# IMU_Raspberry_Pi_Breakout_RevB.net
KiCad netlist of a schematic drawn in EAGLE
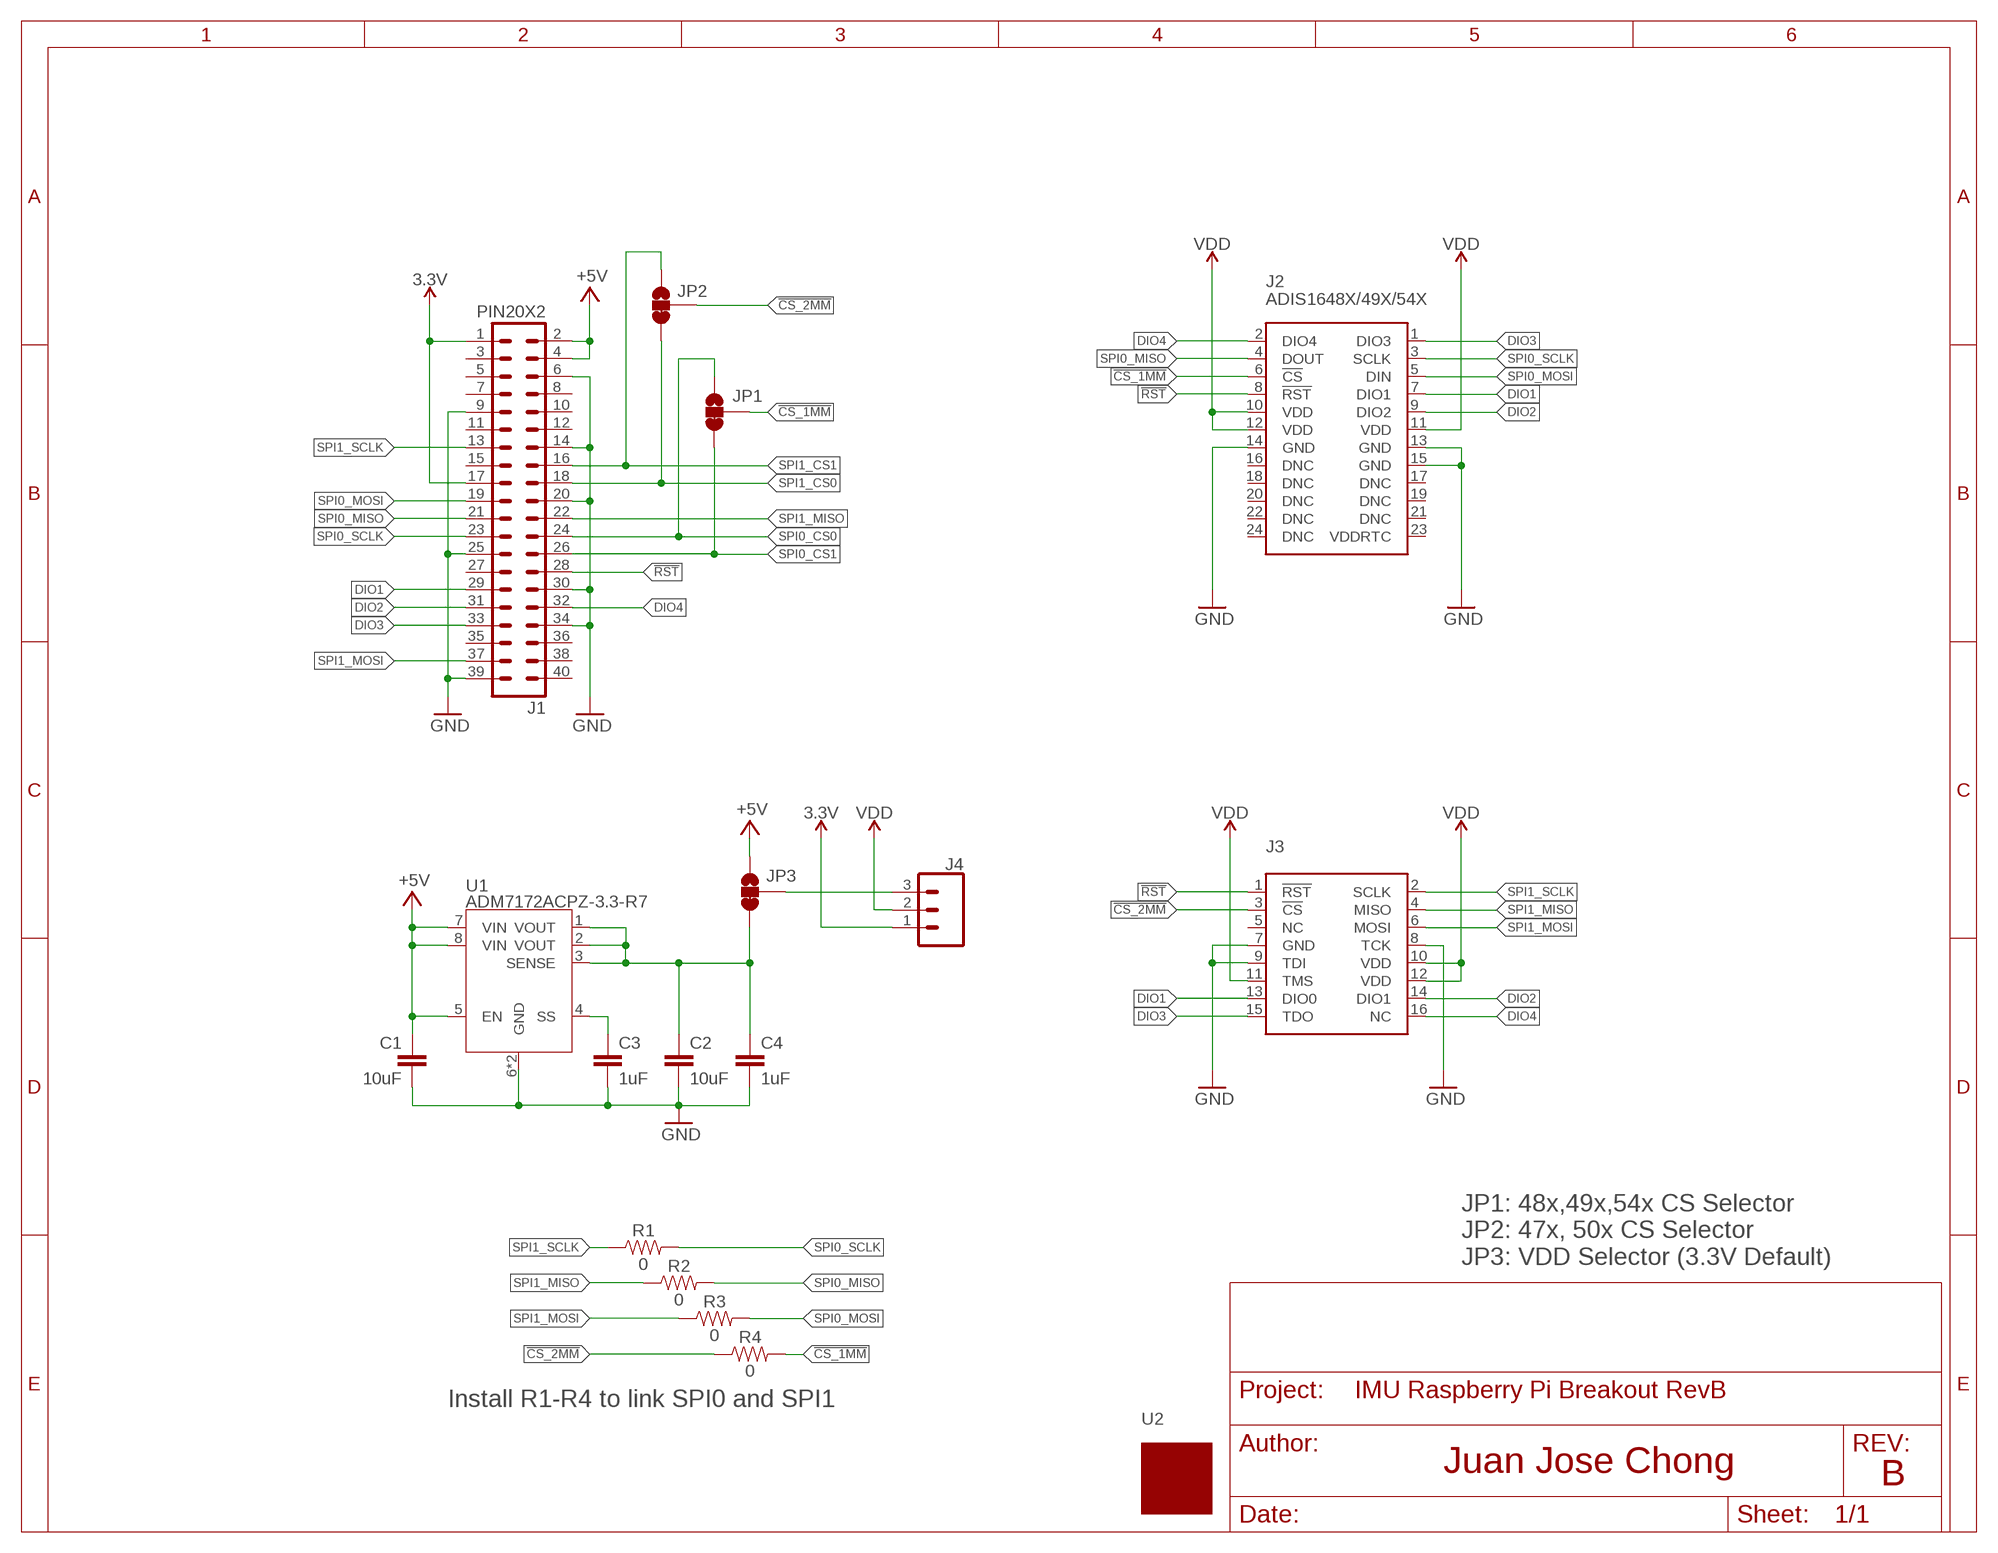
[diagram p0: schematic, sheet 1]

(export (version "E")
  (design (tool "Eeschema 10.0.6"))
  (components
    (comp (ref "C1")
      (value "10uF")
      (footprint "eagle-import:0805")
      (libsource (lib "eagle-import") (part "CAP-0805"))
    )
    (comp (ref "C2")
      (value "10uF")
      (footprint "eagle-import:0805")
      (libsource (lib "eagle-import") (part "CAP-0805"))
    )
    (comp (ref "C3")
      (value "1uF")
      (footprint "eagle-import:0603")
      (libsource (lib "eagle-import") (part "CAP-0603"))
    )
    (comp (ref "C4")
      (value "1uF")
      (footprint "eagle-import:0603")
      (libsource (lib "eagle-import") (part "CAP-0603"))
    )
    (comp (ref "J1")
      (value "PIN20X2")
      (footprint "eagle-import:PIN_20X2")
      (libsource (lib "eagle-import") (part "PIN20X2"))
    )
    (comp (ref "J2")
      (value "ADIS1648X/49X/54X")
      (footprint "eagle-import:ADIS1648X-TAPPED")
      (libsource (lib "eagle-import") (part "ADIS1648X/ADIS1649XTAPPED"))
    )
    (comp (ref "J3")
      (value "ADIS_EVAL_16PIN_2MM")
      (footprint "eagle-import:A3-16PA-2SV(71)-TOP")
      (libsource (lib "eagle-import") (part "ADIS_EVAL_16PIN_2MM"))
    )
    (comp (ref "J4")
      (value "455-1750-1-ND")
      (footprint "eagle-import:1X03")
      (libsource (lib "eagle-import") (part "CONN_03"))
    )
    (comp (ref "JP1")
      (value "JUMPER-SMT_3_1-NC_TRACE_SILK")
      (footprint "eagle-import:SMT-JUMPER_3_1-NC_TRACE_SILK")
      (libsource (lib "eagle-import") (part "JUMPER-SMT_3_1-NC_TRACE_SILK"))
    )
    (comp (ref "JP2")
      (value "JUMPER-SMT_3_1-NC_TRACE_SILK")
      (footprint "eagle-import:SMT-JUMPER_3_1-NC_TRACE_SILK")
      (libsource (lib "eagle-import") (part "JUMPER-SMT_3_1-NC_TRACE_SILK"))
    )
    (comp (ref "JP3")
      (value "JUMPER-SMT_3_1-NC_TRACE_SILK")
      (footprint "eagle-import:SMT-JUMPER_3_1-NC_TRACE_SILK")
      (libsource (lib "eagle-import") (part "JUMPER-SMT_3_1-NC_TRACE_SILK"))
    )
    (comp (ref "R1")
      (value "0")
      (footprint "eagle-import:0603")
      (libsource (lib "eagle-import") (part "RESISTOR0603"))
    )
    (comp (ref "R2")
      (value "0")
      (footprint "eagle-import:0603")
      (libsource (lib "eagle-import") (part "RESISTOR0603"))
    )
    (comp (ref "R3")
      (value "0")
      (footprint "eagle-import:0603")
      (libsource (lib "eagle-import") (part "RESISTOR0603"))
    )
    (comp (ref "R4")
      (value "0")
      (footprint "eagle-import:0603")
      (libsource (lib "eagle-import") (part "RESISTOR0603"))
    )
    (comp (ref "U1")
      (value "ADM7172ACPZ-3.3-R7")
      (footprint "eagle-import:LFCSP-8")
      (libsource (lib "eagle-import") (part "ADM7172ACPZ-3.3-R7"))
    )
    (comp (ref "U2")
      (value "ADIS16XXX_COUPON")
      (footprint "eagle-import:ADIS16XXX_COUPON")
      (libsource (lib "eagle-import") (part "ADIS16XXX_COUPON"))
    )
  )
  (nets
    (net (code "1") (name "+5V") (class "Default")
      (node (ref "C1") (pin "1") (pinfunction "1_1") (pintype "passive"))
      (node (ref "J1") (pin "2") (pinfunction "2_2") (pintype "passive"))
      (node (ref "J1") (pin "4") (pinfunction "4_4") (pintype "passive"))
      (node (ref "JP3") (pin "1") (pinfunction "1_1") (pintype "passive"))
      (node (ref "U1") (pin "5") (pinfunction "EN_5") (pintype "bidirectional"))
      (node (ref "U1") (pin "7") (pinfunction "VIN_7") (pintype "bidirectional"))
      (node (ref "U1") (pin "8") (pinfunction "VIN_8") (pintype "bidirectional"))
    )
    (net (code "2") (name "/~{CS_1MM}") (class "Default")
      (node (ref "J2") (pin "6") (pinfunction "~{CS}_6") (pintype "bidirectional"))
      (node (ref "JP1") (pin "2") (pinfunction "2_2") (pintype "passive"))
      (node (ref "R4") (pin "2") (pinfunction "2_2") (pintype "passive"))
    )
    (net (code "3") (name "/~{CS_2MM}") (class "Default")
      (node (ref "J3") (pin "3") (pinfunction "~{CS}_3") (pintype "bidirectional"))
      (node (ref "JP2") (pin "2") (pinfunction "2_2") (pintype "passive"))
      (node (ref "R4") (pin "1") (pinfunction "1_1") (pintype "passive"))
    )
    (net (code "4") (name "/~{RST}") (class "Default")
      (node (ref "J1") (pin "28") (pinfunction "28_28") (pintype "passive"))
      (node (ref "J2") (pin "8") (pinfunction "~{RST}_8") (pintype "bidirectional"))
      (node (ref "J3") (pin "1") (pinfunction "~{RST}_1") (pintype "bidirectional"))
    )
    (net (code "5") (name "3.3V") (class "Default")
      (node (ref "J1") (pin "1") (pinfunction "1_1") (pintype "passive"))
      (node (ref "J1") (pin "17") (pinfunction "17_17") (pintype "passive"))
      (node (ref "J4") (pin "1") (pinfunction "1_1") (pintype "passive"))
    )
    (net (code "6") (name "DIO1") (class "Default")
      (node (ref "J1") (pin "29") (pinfunction "29_29") (pintype "passive"))
      (node (ref "J2") (pin "7") (pinfunction "DIO1_7") (pintype "bidirectional"))
      (node (ref "J3") (pin "13") (pinfunction "DIO0_13") (pintype "bidirectional"))
    )
    (net (code "7") (name "DIO2") (class "Default")
      (node (ref "J1") (pin "31") (pinfunction "31_31") (pintype "passive"))
      (node (ref "J2") (pin "9") (pinfunction "DIO2_9") (pintype "bidirectional"))
      (node (ref "J3") (pin "14") (pinfunction "DIO1_14") (pintype "bidirectional"))
    )
    (net (code "8") (name "DIO3") (class "Default")
      (node (ref "J1") (pin "33") (pinfunction "33_33") (pintype "passive"))
      (node (ref "J2") (pin "1") (pinfunction "DIO3_1") (pintype "bidirectional"))
      (node (ref "J3") (pin "15") (pinfunction "TDO_15") (pintype "bidirectional"))
    )
    (net (code "9") (name "DIO4") (class "Default")
      (node (ref "J1") (pin "32") (pinfunction "32_32") (pintype "passive"))
      (node (ref "J2") (pin "2") (pinfunction "DIO4_2") (pintype "bidirectional"))
      (node (ref "J3") (pin "16") (pinfunction "NC_16") (pintype "bidirectional"))
    )
    (net (code "10") (name "GND") (class "Default")
      (node (ref "C1") (pin "2") (pinfunction "2_2") (pintype "passive"))
      (node (ref "C2") (pin "2") (pinfunction "2_2") (pintype "passive"))
      (node (ref "C3") (pin "2") (pinfunction "2_2") (pintype "passive"))
      (node (ref "C4") (pin "2") (pinfunction "2_2") (pintype "passive"))
      (node (ref "J1") (pin "14") (pinfunction "14_14") (pintype "passive"))
      (node (ref "J1") (pin "20") (pinfunction "20_20") (pintype "passive"))
      (node (ref "J1") (pin "25") (pinfunction "25_25") (pintype "passive"))
      (node (ref "J1") (pin "30") (pinfunction "30_30") (pintype "passive"))
      (node (ref "J1") (pin "34") (pinfunction "34_34") (pintype "passive"))
      (node (ref "J1") (pin "39") (pinfunction "39_39") (pintype "passive"))
      (node (ref "J1") (pin "6") (pinfunction "6_6") (pintype "passive"))
      (node (ref "J1") (pin "9") (pinfunction "9_9") (pintype "passive"))
      (node (ref "J2") (pin "13") (pinfunction "GND_13") (pintype "bidirectional"))
      (node (ref "J2") (pin "14") (pinfunction "GND_14") (pintype "bidirectional"))
      (node (ref "J2") (pin "15") (pinfunction "GND_15") (pintype "bidirectional"))
      (node (ref "J3") (pin "7") (pinfunction "GND_7") (pintype "bidirectional"))
      (node (ref "J3") (pin "8") (pinfunction "TCK_8") (pintype "bidirectional"))
      (node (ref "J3") (pin "9") (pinfunction "TDI_9") (pintype "bidirectional"))
      (node (ref "U1") (pin "6") (pinfunction "GND_6") (pintype "bidirectional"))
      (node (ref "U1") (pin "9") (pinfunction "GND_9") (pintype "bidirectional"))
    )
    (net (code "11") (name "Net-(J4-Pad3)") (class "Default")
      (node (ref "J4") (pin "3") (pinfunction "3_3") (pintype "passive"))
      (node (ref "JP3") (pin "2") (pinfunction "2_2") (pintype "passive"))
    )
    (net (code "12") (name "Net-(U1-SENSE)") (class "Default")
      (node (ref "C2") (pin "1") (pinfunction "1_1") (pintype "passive"))
      (node (ref "C4") (pin "1") (pinfunction "1_1") (pintype "passive"))
      (node (ref "JP3") (pin "3") (pinfunction "3_3") (pintype "passive"))
      (node (ref "U1") (pin "1") (pinfunction "VOUT_1") (pintype "bidirectional"))
      (node (ref "U1") (pin "2") (pinfunction "VOUT_2") (pintype "bidirectional"))
      (node (ref "U1") (pin "3") (pinfunction "SENSE_3") (pintype "bidirectional"))
    )
    (net (code "13") (name "Net-(U1-SS)") (class "Default")
      (node (ref "C3") (pin "1") (pinfunction "1_1") (pintype "passive"))
      (node (ref "U1") (pin "4") (pinfunction "SS_4") (pintype "bidirectional"))
    )
    (net (code "14") (name "SPI0_CS0") (class "Default")
      (node (ref "J1") (pin "24") (pinfunction "24_24") (pintype "passive"))
      (node (ref "JP1") (pin "1") (pinfunction "1_1") (pintype "passive"))
    )
    (net (code "15") (name "SPI0_CS1") (class "Default")
      (node (ref "J1") (pin "26") (pinfunction "26_26") (pintype "passive"))
      (node (ref "JP1") (pin "3") (pinfunction "3_3") (pintype "passive"))
    )
    (net (code "16") (name "SPI0_MISO") (class "Default")
      (node (ref "J1") (pin "21") (pinfunction "21_21") (pintype "passive"))
      (node (ref "J2") (pin "4") (pinfunction "DOUT_4") (pintype "bidirectional"))
      (node (ref "R2") (pin "2") (pinfunction "2_2") (pintype "passive"))
    )
    (net (code "17") (name "SPI0_MOSI") (class "Default")
      (node (ref "J1") (pin "19") (pinfunction "19_19") (pintype "passive"))
      (node (ref "J2") (pin "5") (pinfunction "DIN_5") (pintype "bidirectional"))
      (node (ref "R3") (pin "2") (pinfunction "2_2") (pintype "passive"))
    )
    (net (code "18") (name "SPI0_SCLK") (class "Default")
      (node (ref "J1") (pin "23") (pinfunction "23_23") (pintype "passive"))
      (node (ref "J2") (pin "3") (pinfunction "SCLK_3") (pintype "bidirectional"))
      (node (ref "R1") (pin "2") (pinfunction "2_2") (pintype "passive"))
    )
    (net (code "19") (name "SPI1_CS0") (class "Default")
      (node (ref "J1") (pin "18") (pinfunction "18_18") (pintype "passive"))
      (node (ref "JP2") (pin "3") (pinfunction "3_3") (pintype "passive"))
    )
    (net (code "20") (name "SPI1_CS1") (class "Default")
      (node (ref "J1") (pin "16") (pinfunction "16_16") (pintype "passive"))
      (node (ref "JP2") (pin "1") (pinfunction "1_1") (pintype "passive"))
    )
    (net (code "21") (name "SPI1_MISO") (class "Default")
      (node (ref "J1") (pin "22") (pinfunction "22_22") (pintype "passive"))
      (node (ref "J3") (pin "4") (pinfunction "MISO_4") (pintype "bidirectional"))
      (node (ref "R2") (pin "1") (pinfunction "1_1") (pintype "passive"))
    )
    (net (code "22") (name "SPI1_MOSI") (class "Default")
      (node (ref "J1") (pin "37") (pinfunction "37_37") (pintype "passive"))
      (node (ref "J3") (pin "6") (pinfunction "MOSI_6") (pintype "bidirectional"))
      (node (ref "R3") (pin "1") (pinfunction "1_1") (pintype "passive"))
    )
    (net (code "23") (name "SPI1_SCLK") (class "Default")
      (node (ref "J1") (pin "13") (pinfunction "13_13") (pintype "passive"))
      (node (ref "J3") (pin "2") (pinfunction "SCLK_2") (pintype "bidirectional"))
      (node (ref "R1") (pin "1") (pinfunction "1_1") (pintype "passive"))
    )
    (net (code "24") (name "VDD") (class "Default")
      (node (ref "J2") (pin "10") (pinfunction "VDD_10") (pintype "bidirectional"))
      (node (ref "J2") (pin "11") (pinfunction "VDD_11") (pintype "bidirectional"))
      (node (ref "J2") (pin "12") (pinfunction "VDD_12") (pintype "bidirectional"))
      (node (ref "J3") (pin "10") (pinfunction "VDD_10") (pintype "bidirectional"))
      (node (ref "J3") (pin "11") (pinfunction "TMS_11") (pintype "bidirectional"))
      (node (ref "J3") (pin "12") (pinfunction "VDD_12") (pintype "bidirectional"))
      (node (ref "J4") (pin "2") (pinfunction "2_2") (pintype "passive"))
    )
    (net (code "25") (name "unconnected-(J1-Pad3)") (class "Default")
      (node (ref "J1") (pin "3") (pinfunction "3_3") (pintype "passive"))
    )
    (net (code "26") (name "unconnected-(J1-Pad5)") (class "Default")
      (node (ref "J1") (pin "5") (pinfunction "5_5") (pintype "passive"))
    )
    (net (code "27") (name "unconnected-(J1-Pad7)") (class "Default")
      (node (ref "J1") (pin "7") (pinfunction "7_7") (pintype "passive"))
    )
    (net (code "28") (name "unconnected-(J1-Pad8)") (class "Default")
      (node (ref "J1") (pin "8") (pinfunction "8_8") (pintype "passive"))
    )
    (net (code "29") (name "unconnected-(J1-Pad10)") (class "Default")
      (node (ref "J1") (pin "10") (pinfunction "10_10") (pintype "passive"))
    )
    (net (code "30") (name "unconnected-(J1-Pad11)") (class "Default")
      (node (ref "J1") (pin "11") (pinfunction "11_11") (pintype "passive"))
    )
    (net (code "31") (name "unconnected-(J1-Pad12)") (class "Default")
      (node (ref "J1") (pin "12") (pinfunction "12_12") (pintype "passive"))
    )
    (net (code "32") (name "unconnected-(J1-Pad15)") (class "Default")
      (node (ref "J1") (pin "15") (pinfunction "15_15") (pintype "passive"))
    )
    (net (code "33") (name "unconnected-(J1-Pad27)") (class "Default")
      (node (ref "J1") (pin "27") (pinfunction "27_27") (pintype "passive"))
    )
    (net (code "34") (name "unconnected-(J1-Pad35)") (class "Default")
      (node (ref "J1") (pin "35") (pinfunction "35_35") (pintype "passive"))
    )
    (net (code "35") (name "unconnected-(J1-Pad36)") (class "Default")
      (node (ref "J1") (pin "36") (pinfunction "36_36") (pintype "passive"))
    )
    (net (code "36") (name "unconnected-(J1-Pad38)") (class "Default")
      (node (ref "J1") (pin "38") (pinfunction "38_38") (pintype "passive"))
    )
    (net (code "37") (name "unconnected-(J1-Pad40)") (class "Default")
      (node (ref "J1") (pin "40") (pinfunction "40_40") (pintype "passive"))
    )
    (net (code "38") (name "unconnected-(J2-DNC-Pad16)") (class "Default")
      (node (ref "J2") (pin "16") (pinfunction "DNC_16") (pintype "bidirectional"))
    )
    (net (code "39") (name "unconnected-(J2-DNC-Pad17)") (class "Default")
      (node (ref "J2") (pin "17") (pinfunction "DNC_17") (pintype "bidirectional"))
    )
    (net (code "40") (name "unconnected-(J2-DNC-Pad18)") (class "Default")
      (node (ref "J2") (pin "18") (pinfunction "DNC_18") (pintype "bidirectional"))
    )
    (net (code "41") (name "unconnected-(J2-DNC-Pad19)") (class "Default")
      (node (ref "J2") (pin "19") (pinfunction "DNC_19") (pintype "bidirectional"))
    )
    (net (code "42") (name "unconnected-(J2-DNC-Pad20)") (class "Default")
      (node (ref "J2") (pin "20") (pinfunction "DNC_20") (pintype "bidirectional"))
    )
    (net (code "43") (name "unconnected-(J2-DNC-Pad21)") (class "Default")
      (node (ref "J2") (pin "21") (pinfunction "DNC_21") (pintype "bidirectional"))
    )
    (net (code "44") (name "unconnected-(J2-DNC-Pad22)") (class "Default")
      (node (ref "J2") (pin "22") (pinfunction "DNC_22") (pintype "bidirectional"))
    )
    (net (code "45") (name "unconnected-(J2-DNC-Pad24)") (class "Default")
      (node (ref "J2") (pin "24") (pinfunction "DNC_24") (pintype "bidirectional"))
    )
    (net (code "46") (name "unconnected-(J2-VDDRTC-Pad23)") (class "Default")
      (node (ref "J2") (pin "23") (pinfunction "VDDRTC_23") (pintype "bidirectional"))
    )
    (net (code "47") (name "unconnected-(J3-NC-Pad5)") (class "Default")
      (node (ref "J3") (pin "5") (pinfunction "NC_5") (pintype "bidirectional"))
    )
  )
)
